# adc.net
KiCad netlist of a schematic drawn in Altium Designer
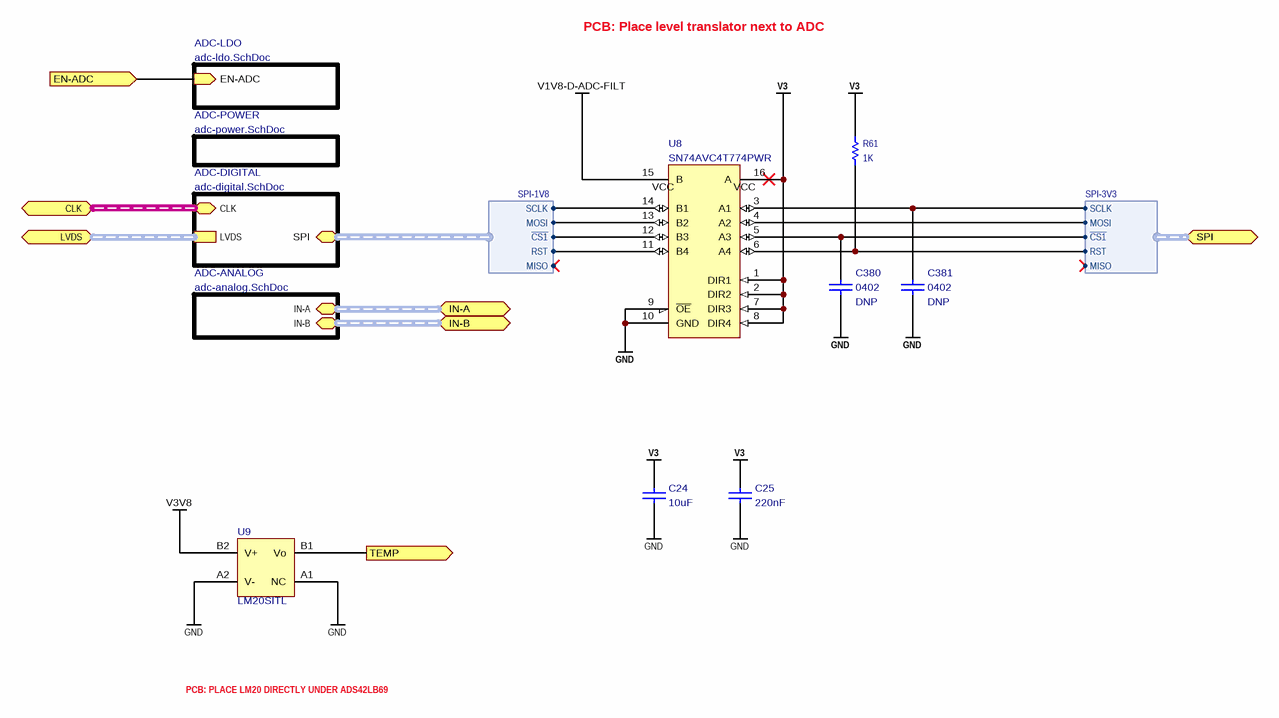
[diagram p0: adc.SchDoc]

(export (version "E")
  (design (tool "Eeschema 10.0.6"))
  (components
    (comp (ref "C24")
      (value "10uF")
      (footprint "CAPC200X125X145L45N")
      (description "Ceramic Capacitor 10uF ±10% 16V X7R 0805")
      (fields (field (name "MANUFACTURER") "Samsung") (field (name "TOLERANCE") "±10%"))
      (libsource (lib "capacitors") (part "CAP"))
    )
    (comp (ref "C25")
      (value "220nF")
      (footprint "CAPC100X50X55L25N")
      (description "Ceramic Capacitor 220nF ±10% 25V X7R 0402")
      (fields (field (name "MANUFACTURER") "TDK") (field (name "TOLERANCE") "±10%"))
      (libsource (lib "capacitors") (part "CAP"))
    )
    (comp (ref "C380")
      (value "VJ0402A101KXA")
      (footprint "CAPC100X50X55L25N")
      (description "Ceramic Capacitor 100pF ±10% 50V C0G 0402")
      (fields
        (field (name "MANUFACTURER") "Vishay")
        (field (name "TOLERANCE") "±10%")
        (field (name "PACKAGE") "0402")
        (field (name "DO NOT PLACE") "DNP")
      )
      (libsource (lib "capacitors") (part "CAP"))
    )
    (comp (ref "C381")
      (value "VJ0402A101KXA")
      (footprint "CAPC100X50X55L25N")
      (description "Ceramic Capacitor 100pF ±10% 50V C0G 0402")
      (fields
        (field (name "MANUFACTURER") "Vishay")
        (field (name "TOLERANCE") "±10%")
        (field (name "PACKAGE") "0402")
        (field (name "DO NOT PLACE") "DNP")
      )
      (libsource (lib "capacitors") (part "CAP"))
    )
    (comp (ref "R61")
      (value "1K")
      (footprint "RESC1005X40N")
      (description "Thick Film Resistor 1k ±1% 0402")
      (fields (field (name "MANUFACTURER") "Yageo") (field (name "TOLERANCE") "±1%"))
      (libsource (lib "Graviton") (part "RES 0402"))
    )
    (comp (ref "U8")
      (value "SN74AVC4T774PWR")
      (footprint "TSSOP16")
      (description "4-Bit Dual-Supply Bus Transceiver")
      (fields (field (name "MANUFACTURER") "Texas Instruments"))
      (libsource (lib "ti") (part "SN74AVC4T774PWR"))
    )
    (comp (ref "U9")
      (value "LM20SITL")
      (footprint "YZR-4")
      (description "Analog Temperature Sensor")
      (fields (field (name "MANUFACTURER") "Texas Instruments"))
      (libsource (lib "ti") (part "LM20SITL"))
    )
  )
  (nets
    (net (code "12") (name "/TEMP") (class "Default")
      (node (ref "U9") (pin "B1") (pinfunction "Vo_B1") (pintype "passive"))
    )
    (net (code "15") (name "GND") (class "Default")
      (node (ref "C24") (pin "2") (pinfunction "2_2") (pintype "passive"))
      (node (ref "C25") (pin "2") (pinfunction "2_2") (pintype "passive"))
      (node (ref "C380") (pin "2") (pinfunction "2_2") (pintype "passive"))
      (node (ref "C381") (pin "2") (pinfunction "2_2") (pintype "passive"))
      (node (ref "U8") (pin "10") (pinfunction "GND_10") (pintype "power_in"))
      (node (ref "U8") (pin "9") (pinfunction "OE_9") (pintype "passive"))
      (node (ref "U9") (pin "A1") (pinfunction "NC_A1") (pintype "passive"))
      (node (ref "U9") (pin "A2") (pinfunction "V-_A2") (pintype "passive"))
    )
    (net (code "16") (name "Net-(U8-A1)") (class "Default")
      (node (ref "C381") (pin "1") (pinfunction "1_1") (pintype "passive"))
      (node (ref "U8") (pin "3") (pinfunction "A1_3") (pintype "bidirectional"))
    )
    (net (code "17") (name "Net-(U8-A3)") (class "Default")
      (node (ref "C380") (pin "1") (pinfunction "1_1") (pintype "passive"))
      (node (ref "U8") (pin "5") (pinfunction "A3_5") (pintype "bidirectional"))
    )
    (net (code "18") (name "Net-(U8-A4)") (class "Default")
      (node (ref "R61") (pin "1") (pinfunction "1_1") (pintype "passive"))
      (node (ref "U8") (pin "6") (pinfunction "A4_6") (pintype "bidirectional"))
    )
    (net (code "19") (name "V1V8-D-ADC-FILT") (class "Default")
      (node (ref "U8") (pin "15") (pinfunction "B_15") (pintype "power_in"))
    )
    (net (code "20") (name "V3") (class "Default")
      (node (ref "C24") (pin "1") (pinfunction "1_1") (pintype "passive"))
      (node (ref "C25") (pin "1") (pinfunction "1_1") (pintype "passive"))
      (node (ref "R61") (pin "2") (pinfunction "2_2") (pintype "passive"))
      (node (ref "U8") (pin "1") (pinfunction "DIR1_1") (pintype "input"))
      (node (ref "U8") (pin "16") (pinfunction "A_16") (pintype "power_in"))
      (node (ref "U8") (pin "2") (pinfunction "DIR2_2") (pintype "input"))
      (node (ref "U8") (pin "7") (pinfunction "DIR3_7") (pintype "input"))
      (node (ref "U8") (pin "8") (pinfunction "DIR4_8") (pintype "input"))
    )
    (net (code "21") (name "V3V8") (class "Default")
      (node (ref "U9") (pin "B2") (pinfunction "V+_B2") (pintype "passive"))
    )
    (net (code "22") (name "unconnected-(U8-A2-Pad4)") (class "Default")
      (node (ref "U8") (pin "4") (pinfunction "A2_4") (pintype "bidirectional"))
    )
    (net (code "23") (name "unconnected-(U8-B1-Pad14)") (class "Default")
      (node (ref "U8") (pin "14") (pinfunction "B1_14") (pintype "bidirectional"))
    )
    (net (code "24") (name "unconnected-(U8-B2-Pad13)") (class "Default")
      (node (ref "U8") (pin "13") (pinfunction "B2_13") (pintype "bidirectional"))
    )
    (net (code "25") (name "unconnected-(U8-B3-Pad12)") (class "Default")
      (node (ref "U8") (pin "12") (pinfunction "B3_12") (pintype "bidirectional"))
    )
    (net (code "26") (name "unconnected-(U8-B4-Pad11)") (class "Default")
      (node (ref "U8") (pin "11") (pinfunction "B4_11") (pintype "bidirectional"))
    )
  )
)
